# RTC.net
KiCad netlist of a schematic drawn in Altium Designer
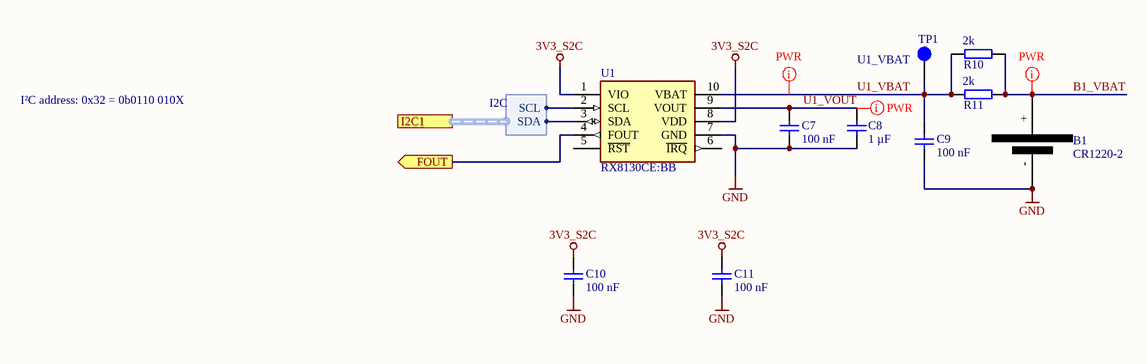
[diagram p0: RTC.SchDoc]

(export (version "E")
  (design (tool "Eeschema 10.0.6"))
  (components
    (comp (ref "B1")
      (value "CR1220-2")
      (footprint "CR1220")
      (description "Battery base CR1220 SMD Button And Strip Battery Connector ROHS")
      (fields
        (field (name "MANUFACTURER") "Q&J")
        (field (name "LCSC PART NUMBER") "C70381")
        (field (name "CREATED FROM") "FRosner")
      )
      (libsource (lib "user") (part "CR1220"))
    )
    (comp (ref "C7")
      (value "100 nF")
      (footprint "C_0603_TE")
      (description "Generic capacitor")
      (fields
        (field (name "TOLERANCE") "10 %")
        (field (name "MANUFACTURER PART NUMBER") "UZgen_C_0603_100nF_50V_X7R")
        (field (name "CREATED FROM") "AGeiger")
      )
      (libsource (lib "user") (part "CAP-NP"))
    )
    (comp (ref "C8")
      (value "1 µF")
      (footprint "C_0603_TE")
      (description "Generic capacitor")
      (fields
        (field (name "MANUFACTURER PART NUMBER") "UZgen_C_0603_1uF_16V_X7R")
        (field (name "MANUFACTURER") "UZgen")
        (field (name "CREATED FROM") "UZgenTool")
      )
      (libsource (lib "user") (part "CAP-NP"))
    )
    (comp (ref "C9")
      (value "100 nF")
      (footprint "C_0603_TE")
      (description "Generic capacitor")
      (fields
        (field (name "TOLERANCE") "10 %")
        (field (name "MANUFACTURER PART NUMBER") "UZgen_C_0603_100nF_50V_X7R")
        (field (name "CREATED FROM") "AGeiger")
      )
      (libsource (lib "user") (part "CAP-NP"))
    )
    (comp (ref "C10")
      (value "100 nF")
      (footprint "C_0603_TE")
      (description "Generic capacitor")
      (fields
        (field (name "TOLERANCE") "10 %")
        (field (name "MANUFACTURER PART NUMBER") "UZgen_C_0603_100nF_50V_X7R")
        (field (name "CREATED FROM") "AGeiger")
      )
      (libsource (lib "user") (part "CAP-NP"))
    )
    (comp (ref "C11")
      (value "100 nF")
      (footprint "C_0603_TE")
      (description "Generic capacitor")
      (fields
        (field (name "TOLERANCE") "10 %")
        (field (name "MANUFACTURER PART NUMBER") "UZgen_C_0603_100nF_50V_X7R")
        (field (name "CREATED FROM") "AGeiger")
      )
      (libsource (lib "user") (part "CAP-NP"))
    )
    (comp (ref "R10")
      (value "2k")
      (footprint "R_0603_TE")
      (description "Generic resistor")
      (fields
        (field (name "MANUFACTURER PART NUMBER") "UZgen_R_0603_2k")
        (field (name "MANUFACTURER") "UZgen")
        (field (name "CREATED FROM") "UZgenTool")
      )
      (libsource (lib "user") (part "RES"))
    )
    (comp (ref "R11")
      (value "2k")
      (footprint "R_0603_TE")
      (description "Generic resistor")
      (fields
        (field (name "MANUFACTURER PART NUMBER") "UZgen_R_0603_2k")
        (field (name "MANUFACTURER") "UZgen")
        (field (name "CREATED FROM") "UZgenTool")
      )
      (libsource (lib "user") (part "RES"))
    )
    (comp (ref "TP1")
      (value "U1_VBAT")
      (footprint "TP_1mm")
      (description "Testpoint 1mm")
      (fields
        (field (name "MANUFACTURER PART NUMBER") "NULL")
        (field (name "CREATED") "2018_06_25_AGeiger")
        (field (name "CREATED FROM") "AGeiger")
      )
      (libsource (lib "user") (part "TP_1mm"))
    )
    (comp (ref "U1")
      (value "RX8130CE:BB")
      (footprint "RX8130CE")
      (description "I2C SMD-10P Real Time Clocks ROHS")
      (fields
        (field (name "MANUFACTURER") "Seiko Epson")
        (field (name "LCSC PART NUMBER") "C1542426")
        (field (name "CREATED FROM") "FRosner")
      )
      (libsource (lib "user") (part "RX8130CE"))
    )
  )
  (nets
    (net (code "2") (name "/B1_VBAT") (class "Default")
      (node (ref "B1") (pin "+") (pinfunction "+_+") (pintype "power_in"))
      (node (ref "R10") (pin "2") (pinfunction "2_2") (pintype "passive"))
      (node (ref "R11") (pin "2") (pinfunction "2_2") (pintype "passive"))
    )
    (net (code "3") (name "/FOUT") (class "Default")
      (node (ref "U1") (pin "4") (pinfunction "FOUT_4") (pintype "output"))
    )
    (net (code "4") (name "/SCL") (class "Default")
      (node (ref "U1") (pin "2") (pinfunction "SCL_2") (pintype "input"))
    )
    (net (code "5") (name "/SDA") (class "Default")
      (node (ref "U1") (pin "3") (pinfunction "SDA_3") (pintype "bidirectional"))
    )
    (net (code "6") (name "/U1_VBAT") (class "Default")
      (node (ref "C9") (pin "1") (pinfunction "1_1") (pintype "passive"))
      (node (ref "R10") (pin "1") (pinfunction "1_1") (pintype "passive"))
      (node (ref "R11") (pin "1") (pinfunction "1_1") (pintype "passive"))
      (node (ref "TP1") (pin "1") (pintype "passive"))
      (node (ref "U1") (pin "10") (pinfunction "VBAT_10") (pintype "passive"))
    )
    (net (code "7") (name "/U1_VOUT") (class "Default")
      (node (ref "C7") (pin "1") (pinfunction "1_1") (pintype "passive"))
      (node (ref "C8") (pin "2") (pinfunction "2_2") (pintype "passive"))
      (node (ref "U1") (pin "9") (pinfunction "VOUT_9") (pintype "passive"))
    )
    (net (code "9") (name "3V3_S2C") (class "Default")
      (node (ref "C10") (pin "1") (pinfunction "1_1") (pintype "passive"))
      (node (ref "C11") (pin "1") (pinfunction "1_1") (pintype "passive"))
      (node (ref "U1") (pin "1") (pinfunction "VIO_1") (pintype "passive"))
      (node (ref "U1") (pin "8") (pinfunction "VDD_8") (pintype "passive"))
    )
    (net (code "10") (name "GND") (class "Default")
      (node (ref "B1") (pin "-") (pinfunction "-_-") (pintype "power_in"))
      (node (ref "C10") (pin "2") (pinfunction "2_2") (pintype "passive"))
      (node (ref "C11") (pin "2") (pinfunction "2_2") (pintype "passive"))
      (node (ref "C7") (pin "2") (pinfunction "2_2") (pintype "passive"))
      (node (ref "C8") (pin "1") (pinfunction "1_1") (pintype "passive"))
      (node (ref "C9") (pin "2") (pinfunction "2_2") (pintype "passive"))
      (node (ref "U1") (pin "7") (pinfunction "GND_7") (pintype "passive"))
    )
    (net (code "11") (name "unconnected-(U1-~{IRQ}-Pad6)") (class "Default")
      (node (ref "U1") (pin "6") (pinfunction "~{IRQ}_6") (pintype "output"))
    )
    (net (code "12") (name "unconnected-(U1-~{RST}-Pad5)") (class "Default")
      (node (ref "U1") (pin "5") (pinfunction "~{RST}_5") (pintype "passive"))
    )
  )
)
